# main.net
KiCad netlist of a schematic drawn in EAGLE
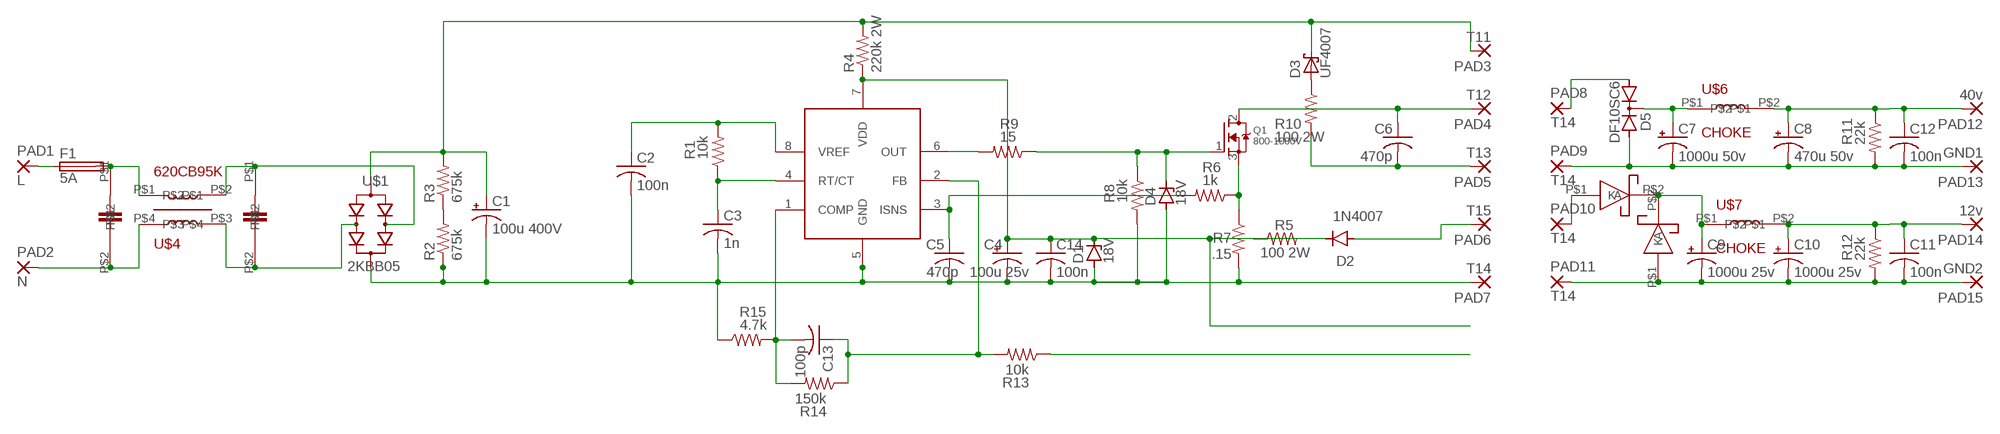
[diagram p0: schematic, sheet 1]

(export (version "E")
  (design (tool "Eeschema 10.0.6"))
  (components
    (comp (ref "C1")
      (value "100u 400V")
      (footprint "eagle-import:EB25D")
      (libsource (lib "eagle-import") (part "CPOL-USE10-25"))
    )
    (comp (ref "C2")
      (value "100n")
      (footprint "eagle-import:C050-035X075")
      (libsource (lib "eagle-import") (part "C-US050-035X075"))
    )
    (comp (ref "C3")
      (value "1n")
      (footprint "eagle-import:C050-035X075")
      (libsource (lib "eagle-import") (part "C-US050-035X075"))
    )
    (comp (ref "C4")
      (value "100u 25v")
      (footprint "eagle-import:E2,5-6")
      (libsource (lib "eagle-import") (part "CPOL-USE2.5-6"))
    )
    (comp (ref "C5")
      (value "470p")
      (footprint "eagle-import:C050-035X075")
      (libsource (lib "eagle-import") (part "C-US050-035X075"))
    )
    (comp (ref "C6")
      (value "470p")
      (footprint "eagle-import:C050-035X075")
      (libsource (lib "eagle-import") (part "C-US050-035X075"))
    )
    (comp (ref "C7")
      (value "1000u 50v")
      (footprint "eagle-import:E5-13")
      (libsource (lib "eagle-import") (part "CPOL-USE5-13"))
    )
    (comp (ref "C8")
      (value "470u 50v")
      (footprint "eagle-import:E5-10,5")
      (libsource (lib "eagle-import") (part "CPOL-USE5-10.5"))
    )
    (comp (ref "C9")
      (value "1000u 25v")
      (footprint "eagle-import:E5-10,5")
      (libsource (lib "eagle-import") (part "CPOL-USE5-10.5"))
    )
    (comp (ref "C10")
      (value "1000u 25v")
      (footprint "eagle-import:E5-10,5")
      (libsource (lib "eagle-import") (part "CPOL-USE5-10.5"))
    )
    (comp (ref "C11")
      (value "100n")
      (footprint "eagle-import:C050-035X075")
      (libsource (lib "eagle-import") (part "C-US050-035X075"))
    )
    (comp (ref "C12")
      (value "100n")
      (footprint "eagle-import:C050-035X075")
      (libsource (lib "eagle-import") (part "C-US050-035X075"))
    )
    (comp (ref "C13")
      (value "100p")
      (footprint "eagle-import:C050-035X075")
      (libsource (lib "eagle-import") (part "C-US050-035X075"))
    )
    (comp (ref "C14")
      (value "100n")
      (footprint "eagle-import:C050-035X075")
      (libsource (lib "eagle-import") (part "C-US050-035X075"))
    )
    (comp (ref "D1")
      (value "18V")
      (footprint "eagle-import:ZDIO-7.5")
      (libsource (lib "eagle-import") (part "ZENER-DIODEZD-7.5"))
    )
    (comp (ref "D2")
      (value "1N4007")
      (footprint "eagle-import:DO41-10")
      (libsource (lib "eagle-import") (part "1N4004"))
    )
    (comp (ref "D3")
      (value "UF4007")
      (footprint "eagle-import:DO35-7")
      (libsource (lib "eagle-import") (part "SCHOTTKY-DIODEDO35-7"))
    )
    (comp (ref "D4")
      (value "18V")
      (footprint "eagle-import:ZDIO-7.5")
      (libsource (lib "eagle-import") (part "ZENER-DIODEZD-7.5"))
    )
    (comp (ref "D5")
      (value "DF10SC6")
      (footprint "eagle-import:TO220ABS")
      (libsource (lib "eagle-import") (part "BYV32"))
    )
    (comp (ref "D7")
      (value "SS34")
      (footprint "eagle-import:DO-214AB")
      (libsource (lib "eagle-import") (part "SS34"))
    )
    (comp (ref "D8")
      (value "SS34")
      (footprint "eagle-import:DO-214AB")
      (libsource (lib "eagle-import") (part "SS34"))
    )
    (comp (ref "F1")
      (value "5A")
      (footprint "eagle-import:SH22,5")
      (fields (field (name "MF") "SCHURTER") (field (name "MPN") "0031.8201"))
      (libsource (lib "eagle-import") (part "SH22,5"))
    )
    (comp (ref "PAD1")
      (value "L")
      (footprint "eagle-import:2,54_1,0")
      (libsource (lib "eagle-import") (part "2,54/1,0"))
    )
    (comp (ref "PAD2")
      (value "N")
      (footprint "eagle-import:2,54_1,0")
      (libsource (lib "eagle-import") (part "2,54/1,0"))
    )
    (comp (ref "PAD3")
      (value "T11")
      (footprint "eagle-import:2,54_1,0")
      (libsource (lib "eagle-import") (part "2,54/1,0"))
    )
    (comp (ref "PAD4")
      (value "T12")
      (footprint "eagle-import:2,54_1,0")
      (libsource (lib "eagle-import") (part "2,54/1,0"))
    )
    (comp (ref "PAD5")
      (value "T13")
      (footprint "eagle-import:2,54_1,0")
      (libsource (lib "eagle-import") (part "2,54/1,0"))
    )
    (comp (ref "PAD6")
      (value "T15")
      (footprint "eagle-import:2,54_1,0")
      (libsource (lib "eagle-import") (part "2,54/1,0"))
    )
    (comp (ref "PAD7")
      (value "T14")
      (footprint "eagle-import:2,54_1,0")
      (libsource (lib "eagle-import") (part "2,54/1,0"))
    )
    (comp (ref "PAD8")
      (value "T14")
      (footprint "eagle-import:2,54_1,0")
      (libsource (lib "eagle-import") (part "2,54/1,0"))
    )
    (comp (ref "PAD9")
      (value "T14")
      (footprint "eagle-import:2,54_1,0")
      (libsource (lib "eagle-import") (part "2,54/1,0"))
    )
    (comp (ref "PAD10")
      (value "T14")
      (footprint "eagle-import:2,54_1,0")
      (libsource (lib "eagle-import") (part "2,54/1,0"))
    )
    (comp (ref "PAD11")
      (value "T14")
      (footprint "eagle-import:2,54_1,0")
      (libsource (lib "eagle-import") (part "2,54/1,0"))
    )
    (comp (ref "PAD12")
      (value "40v")
      (footprint "eagle-import:2,54_1,0")
      (libsource (lib "eagle-import") (part "2,54/1,0"))
    )
    (comp (ref "PAD13")
      (value "GND1")
      (footprint "eagle-import:2,54_1,0")
      (libsource (lib "eagle-import") (part "2,54/1,0"))
    )
    (comp (ref "PAD14")
      (value "12v")
      (footprint "eagle-import:2,54_1,0")
      (libsource (lib "eagle-import") (part "2,54/1,0"))
    )
    (comp (ref "PAD15")
      (value "GND2")
      (footprint "eagle-import:2,54_1,0")
      (libsource (lib "eagle-import") (part "2,54/1,0"))
    )
    (comp (ref "Q1")
      (value "800-1000V")
      (footprint "eagle-import:TO220V")
      (libsource (lib "eagle-import") (part "MOSFET-NGDS_TO220V"))
    )
    (comp (ref "R1")
      (value "10k")
      (footprint "eagle-import:0207_7")
      (libsource (lib "eagle-import") (part "R-US_0207/7"))
    )
    (comp (ref "R2")
      (value "675k")
      (footprint "eagle-import:0207_7")
      (libsource (lib "eagle-import") (part "R-US_0207/7"))
    )
    (comp (ref "R3")
      (value "675k")
      (footprint "eagle-import:0207_7")
      (libsource (lib "eagle-import") (part "R-US_0207/7"))
    )
    (comp (ref "R4")
      (value "220k 2W")
      (footprint "eagle-import:P0613_15")
      (libsource (lib "eagle-import") (part "R-US_0613/15"))
    )
    (comp (ref "R5")
      (value "100 2W")
      (footprint "eagle-import:0617V")
      (libsource (lib "eagle-import") (part "R-US_0617/5V"))
    )
    (comp (ref "R6")
      (value "1k")
      (footprint "eagle-import:0207_10")
      (libsource (lib "eagle-import") (part "R-US_0207/10"))
    )
    (comp (ref "R7")
      (value ".15")
      (footprint "eagle-import:0207_7")
      (libsource (lib "eagle-import") (part "R-US_0207/7"))
    )
    (comp (ref "R8")
      (value "10k")
      (footprint "eagle-import:0207_7")
      (libsource (lib "eagle-import") (part "R-US_0207/7"))
    )
    (comp (ref "R9")
      (value "15")
      (footprint "eagle-import:0207_7")
      (libsource (lib "eagle-import") (part "R-US_0207/7"))
    )
    (comp (ref "R10")
      (value "100 2W")
      (footprint "eagle-import:0617V")
      (libsource (lib "eagle-import") (part "R-US_0617/5V"))
    )
    (comp (ref "R11")
      (value "22k")
      (footprint "eagle-import:0207_7")
      (libsource (lib "eagle-import") (part "R-US_0207/7"))
    )
    (comp (ref "R12")
      (value "22k")
      (footprint "eagle-import:0207_7")
      (libsource (lib "eagle-import") (part "R-US_0207/7"))
    )
    (comp (ref "R13")
      (value "10k")
      (footprint "eagle-import:0207_7")
      (libsource (lib "eagle-import") (part "R-US_0207/7"))
    )
    (comp (ref "R14")
      (value "150k")
      (footprint "eagle-import:0207_7")
      (libsource (lib "eagle-import") (part "R-US_0207/7"))
    )
    (comp (ref "R15")
      (value "4.7k")
      (footprint "eagle-import:0207_2V")
      (libsource (lib "eagle-import") (part "R-US_0207/2V"))
    )
    (comp (ref "U$1")
      (value "2KBB05")
      (footprint "eagle-import:2KBB05")
      (libsource (lib "eagle-import") (part "2KBB05"))
    )
    (comp (ref "U$2")
      (value "100n")
      (footprint "eagle-import:C_X2")
      (libsource (lib "eagle-import") (part "C_X2"))
    )
    (comp (ref "U$3")
      (value "100n")
      (footprint "eagle-import:C_X2")
      (libsource (lib "eagle-import") (part "C_X2"))
    )
    (comp (ref "U$4")
      (value "620CB95K")
      (footprint "eagle-import:602CB95K")
      (libsource (lib "eagle-import") (part "620CB95K"))
    )
    (comp (ref "U$5")
      (value "MIC3844")
      (footprint "eagle-import:DIL08")
      (libsource (lib "eagle-import") (part "MIC3844"))
    )
    (comp (ref "U$6")
      (value "CHOKE")
      (footprint "eagle-import:CHOKE")
      (libsource (lib "eagle-import") (part "CHOKE"))
    )
    (comp (ref "U$7")
      (value "CHOKE")
      (footprint "eagle-import:CHOKE")
      (libsource (lib "eagle-import") (part "CHOKE"))
    )
  )
  (nets
    (net (code "1") (name "Net-(C7-Pad+)") (class "Default")
      (node (ref "C7") (pin "+") (pinfunction "+_+") (pintype "passive"))
      (node (ref "D5") (pin "C") (pinfunction "C_C") (pintype "passive"))
      (node (ref "U$6") (pin "P$1") (pinfunction "P$1_P$1") (pintype "bidirectional"))
    )
    (net (code "2") (name "Net-(D2-PadC)") (class "Default")
      (node (ref "D2") (pin "C") (pinfunction "C_C") (pintype "passive"))
      (node (ref "R5") (pin "1") (pinfunction "1_1") (pintype "passive"))
    )
    (net (code "3") (name "Net-(D3-PadA)") (class "Default")
      (node (ref "D3") (pin "A") (pinfunction "A_A") (pintype "passive"))
      (node (ref "R10") (pin "1") (pinfunction "1_1") (pintype "passive"))
    )
    (net (code "4") (name "Net-(D7-A)") (class "Default")
      (node (ref "C10") (pin "-") (pinfunction "-_-") (pintype "passive"))
      (node (ref "C11") (pin "2") (pinfunction "2_2") (pintype "passive"))
      (node (ref "C9") (pin "-") (pinfunction "-_-") (pintype "passive"))
      (node (ref "D7") (pin "P$1") (pinfunction "A_P$1") (pintype "bidirectional"))
      (node (ref "PAD11") (pin "1") (pinfunction "P_1") (pintype "passive"))
      (node (ref "PAD15") (pin "1") (pinfunction "P_1") (pintype "passive"))
      (node (ref "R12") (pin "2") (pinfunction "2_2") (pintype "passive"))
    )
    (net (code "5") (name "Net-(D7-K)") (class "Default")
      (node (ref "C9") (pin "+") (pinfunction "+_+") (pintype "passive"))
      (node (ref "D7") (pin "P$2") (pinfunction "K_P$2") (pintype "bidirectional"))
      (node (ref "D8") (pin "P$2") (pinfunction "K_P$2") (pintype "bidirectional"))
      (node (ref "U$7") (pin "P$1") (pinfunction "P$1_P$1") (pintype "bidirectional"))
    )
    (net (code "6") (name "Net-(D8-A)") (class "Default")
      (node (ref "D8") (pin "P$1") (pinfunction "A_P$1") (pintype "bidirectional"))
      (node (ref "PAD10") (pin "1") (pinfunction "P_1") (pintype "passive"))
    )
    (net (code "7") (name "Net-(F1-Pad2)") (class "Default")
      (node (ref "F1") (pin "2") (pinfunction "2_2") (pintype "passive"))
      (node (ref "U$3") (pin "P$1") (pinfunction "P$1_P$1") (pintype "bidirectional"))
      (node (ref "U$4") (pin "P$1") (pinfunction "P$1_P$1") (pintype "bidirectional"))
    )
    (net (code "8") (name "Net-(PAD1-P)") (class "Default")
      (node (ref "F1") (pin "1") (pinfunction "1_1") (pintype "passive"))
      (node (ref "PAD1") (pin "1") (pinfunction "P_1") (pintype "passive"))
    )
    (net (code "9") (name "Net-(PAD2-P)") (class "Default")
      (node (ref "PAD2") (pin "1") (pinfunction "P_1") (pintype "passive"))
      (node (ref "U$3") (pin "P$2") (pinfunction "P$2_P$2") (pintype "bidirectional"))
      (node (ref "U$4") (pin "P$4") (pinfunction "P$4_P$4") (pintype "bidirectional"))
    )
    (net (code "10") (name "Net-(PAD3-P)") (class "Default")
      (node (ref "C1") (pin "+") (pinfunction "+_+") (pintype "passive"))
      (node (ref "D3") (pin "C") (pinfunction "C_C") (pintype "passive"))
      (node (ref "PAD3") (pin "1") (pinfunction "P_1") (pintype "passive"))
      (node (ref "R3") (pin "2") (pinfunction "2_2") (pintype "passive"))
      (node (ref "R4") (pin "2") (pinfunction "2_2") (pintype "passive"))
      (node (ref "U$1") (pin "-") (pinfunction "-_-") (pintype "passive"))
    )
    (net (code "11") (name "Net-(PAD4-P)") (class "Default")
      (node (ref "C6") (pin "1") (pinfunction "1_1") (pintype "passive"))
      (node (ref "PAD4") (pin "1") (pinfunction "P_1") (pintype "passive"))
      (node (ref "Q1") (pin "2") (pinfunction "D_2") (pintype "bidirectional"))
    )
    (net (code "12") (name "Net-(PAD5-P)") (class "Default")
      (node (ref "C6") (pin "2") (pinfunction "2_2") (pintype "passive"))
      (node (ref "PAD5") (pin "1") (pinfunction "P_1") (pintype "passive"))
      (node (ref "R10") (pin "2") (pinfunction "2_2") (pintype "passive"))
    )
    (net (code "13") (name "Net-(PAD6-P)") (class "Default")
      (node (ref "D2") (pin "A") (pinfunction "A_A") (pintype "passive"))
      (node (ref "PAD6") (pin "1") (pinfunction "P_1") (pintype "passive"))
    )
    (net (code "14") (name "Net-(PAD7-P)") (class "Default")
      (node (ref "C1") (pin "-") (pinfunction "-_-") (pintype "passive"))
      (node (ref "C14") (pin "2") (pinfunction "2_2") (pintype "passive"))
      (node (ref "C2") (pin "2") (pinfunction "2_2") (pintype "passive"))
      (node (ref "C3") (pin "2") (pinfunction "2_2") (pintype "passive"))
      (node (ref "C4") (pin "-") (pinfunction "-_-") (pintype "passive"))
      (node (ref "C5") (pin "2") (pinfunction "2_2") (pintype "passive"))
      (node (ref "D1") (pin "A") (pinfunction "A_A") (pintype "passive"))
      (node (ref "D4") (pin "A") (pinfunction "A_A") (pintype "passive"))
      (node (ref "PAD7") (pin "1") (pinfunction "P_1") (pintype "passive"))
      (node (ref "R15") (pin "1") (pinfunction "1_1") (pintype "passive"))
      (node (ref "R2") (pin "1") (pinfunction "1_1") (pintype "passive"))
      (node (ref "R7") (pin "2") (pinfunction "2_2") (pintype "passive"))
      (node (ref "R8") (pin "2") (pinfunction "2_2") (pintype "passive"))
      (node (ref "U$1") (pin "+") (pinfunction "+_+") (pintype "passive"))
      (node (ref "U$5") (pin "5") (pinfunction "GND_5") (pintype "bidirectional"))
    )
    (net (code "15") (name "Net-(PAD8-P)") (class "Default")
      (node (ref "D5") (pin "A1") (pinfunction "A1_A1") (pintype "passive"))
      (node (ref "PAD8") (pin "1") (pinfunction "P_1") (pintype "passive"))
    )
    (net (code "16") (name "Net-(PAD12-P)") (class "Default")
      (node (ref "C12") (pin "1") (pinfunction "1_1") (pintype "passive"))
      (node (ref "C8") (pin "+") (pinfunction "+_+") (pintype "passive"))
      (node (ref "PAD12") (pin "1") (pinfunction "P_1") (pintype "passive"))
      (node (ref "R11") (pin "1") (pinfunction "1_1") (pintype "passive"))
      (node (ref "U$6") (pin "P$2") (pinfunction "P$2_P$2") (pintype "bidirectional"))
    )
    (net (code "17") (name "Net-(PAD13-P)") (class "Default")
      (node (ref "C12") (pin "2") (pinfunction "2_2") (pintype "passive"))
      (node (ref "C7") (pin "-") (pinfunction "-_-") (pintype "passive"))
      (node (ref "C8") (pin "-") (pinfunction "-_-") (pintype "passive"))
      (node (ref "D5") (pin "A2") (pinfunction "A2_A2") (pintype "passive"))
      (node (ref "PAD13") (pin "1") (pinfunction "P_1") (pintype "passive"))
      (node (ref "PAD9") (pin "1") (pinfunction "P_1") (pintype "passive"))
      (node (ref "R11") (pin "2") (pinfunction "2_2") (pintype "passive"))
    )
    (net (code "18") (name "Net-(PAD14-P)") (class "Default")
      (node (ref "C10") (pin "+") (pinfunction "+_+") (pintype "passive"))
      (node (ref "C11") (pin "1") (pinfunction "1_1") (pintype "passive"))
      (node (ref "PAD14") (pin "1") (pinfunction "P_1") (pintype "passive"))
      (node (ref "R12") (pin "1") (pinfunction "1_1") (pintype "passive"))
      (node (ref "U$7") (pin "P$2") (pinfunction "P$2_P$2") (pintype "bidirectional"))
    )
    (net (code "19") (name "Net-(Q1-G)") (class "Default")
      (node (ref "D4") (pin "C") (pinfunction "C_C") (pintype "passive"))
      (node (ref "Q1") (pin "1") (pinfunction "G_1") (pintype "bidirectional"))
      (node (ref "R8") (pin "1") (pinfunction "1_1") (pintype "passive"))
      (node (ref "R9") (pin "1") (pinfunction "1_1") (pintype "passive"))
    )
    (net (code "20") (name "Net-(Q1-S)") (class "Default")
      (node (ref "Q1") (pin "3") (pinfunction "S_3") (pintype "bidirectional"))
      (node (ref "R6") (pin "1") (pinfunction "1_1") (pintype "passive"))
      (node (ref "R7") (pin "1") (pinfunction "1_1") (pintype "passive"))
    )
    (net (code "21") (name "Net-(R2-Pad2)") (class "Default")
      (node (ref "R2") (pin "2") (pinfunction "2_2") (pintype "passive"))
      (node (ref "R3") (pin "1") (pinfunction "1_1") (pintype "passive"))
    )
    (net (code "22") (name "Net-(U$1-AC-PadAC@1)") (class "Default")
      (node (ref "U$1") (pin "AC@1") (pinfunction "AC_AC@1") (pintype "passive"))
      (node (ref "U$2") (pin "P$2") (pinfunction "P$2_P$2") (pintype "bidirectional"))
      (node (ref "U$4") (pin "P$3") (pinfunction "P$3_P$3") (pintype "bidirectional"))
    )
    (net (code "23") (name "Net-(U$1-AC-PadAC@2)") (class "Default")
      (node (ref "U$1") (pin "AC@2") (pinfunction "AC_AC@2") (pintype "passive"))
      (node (ref "U$2") (pin "P$1") (pinfunction "P$1_P$1") (pintype "bidirectional"))
      (node (ref "U$4") (pin "P$2") (pinfunction "P$2_P$2") (pintype "bidirectional"))
    )
    (net (code "24") (name "Net-(U$5-COMP)") (class "Default")
      (node (ref "C13") (pin "2") (pinfunction "2_2") (pintype "passive"))
      (node (ref "R14") (pin "2") (pinfunction "2_2") (pintype "passive"))
      (node (ref "R15") (pin "2") (pinfunction "2_2") (pintype "passive"))
      (node (ref "U$5") (pin "1") (pinfunction "COMP_1") (pintype "bidirectional"))
    )
    (net (code "25") (name "Net-(U$5-FB)") (class "Default")
      (node (ref "C13") (pin "1") (pinfunction "1_1") (pintype "passive"))
      (node (ref "R13") (pin "2") (pinfunction "2_2") (pintype "passive"))
      (node (ref "R14") (pin "1") (pinfunction "1_1") (pintype "passive"))
      (node (ref "U$5") (pin "2") (pinfunction "FB_2") (pintype "bidirectional"))
    )
    (net (code "26") (name "Net-(U$5-ISNS)") (class "Default")
      (node (ref "C5") (pin "1") (pinfunction "1_1") (pintype "passive"))
      (node (ref "R6") (pin "2") (pinfunction "2_2") (pintype "passive"))
      (node (ref "U$5") (pin "3") (pinfunction "ISNS_3") (pintype "bidirectional"))
    )
    (net (code "27") (name "Net-(U$5-OUT)") (class "Default")
      (node (ref "R9") (pin "2") (pinfunction "2_2") (pintype "passive"))
      (node (ref "U$5") (pin "6") (pinfunction "OUT_6") (pintype "bidirectional"))
    )
    (net (code "28") (name "Net-(U$5-RT{slash}CT)") (class "Default")
      (node (ref "C3") (pin "1") (pinfunction "1_1") (pintype "passive"))
      (node (ref "R1") (pin "1") (pinfunction "1_1") (pintype "passive"))
      (node (ref "U$5") (pin "4") (pinfunction "RT/CT_4") (pintype "bidirectional"))
    )
    (net (code "29") (name "Net-(U$5-VDD)") (class "Default")
      (node (ref "C14") (pin "1") (pinfunction "1_1") (pintype "passive"))
      (node (ref "C4") (pin "+") (pinfunction "+_+") (pintype "passive"))
      (node (ref "D1") (pin "C") (pinfunction "C_C") (pintype "passive"))
      (node (ref "R4") (pin "1") (pinfunction "1_1") (pintype "passive"))
      (node (ref "R5") (pin "2") (pinfunction "2_2") (pintype "passive"))
      (node (ref "U$5") (pin "7") (pinfunction "VDD_7") (pintype "bidirectional"))
    )
    (net (code "30") (name "Net-(U$5-VREF)") (class "Default")
      (node (ref "C2") (pin "1") (pinfunction "1_1") (pintype "passive"))
      (node (ref "R1") (pin "2") (pinfunction "2_2") (pintype "passive"))
      (node (ref "U$5") (pin "8") (pinfunction "VREF_8") (pintype "bidirectional"))
    )
    (net (code "31") (name "unconnected-(R13-Pad1)") (class "Default")
      (node (ref "R13") (pin "1") (pinfunction "1_1") (pintype "passive"))
    )
  )
)
